# IO_Shield_With_Power_Supply_PCB.net
KiCad netlist of a schematic drawn in EAGLE
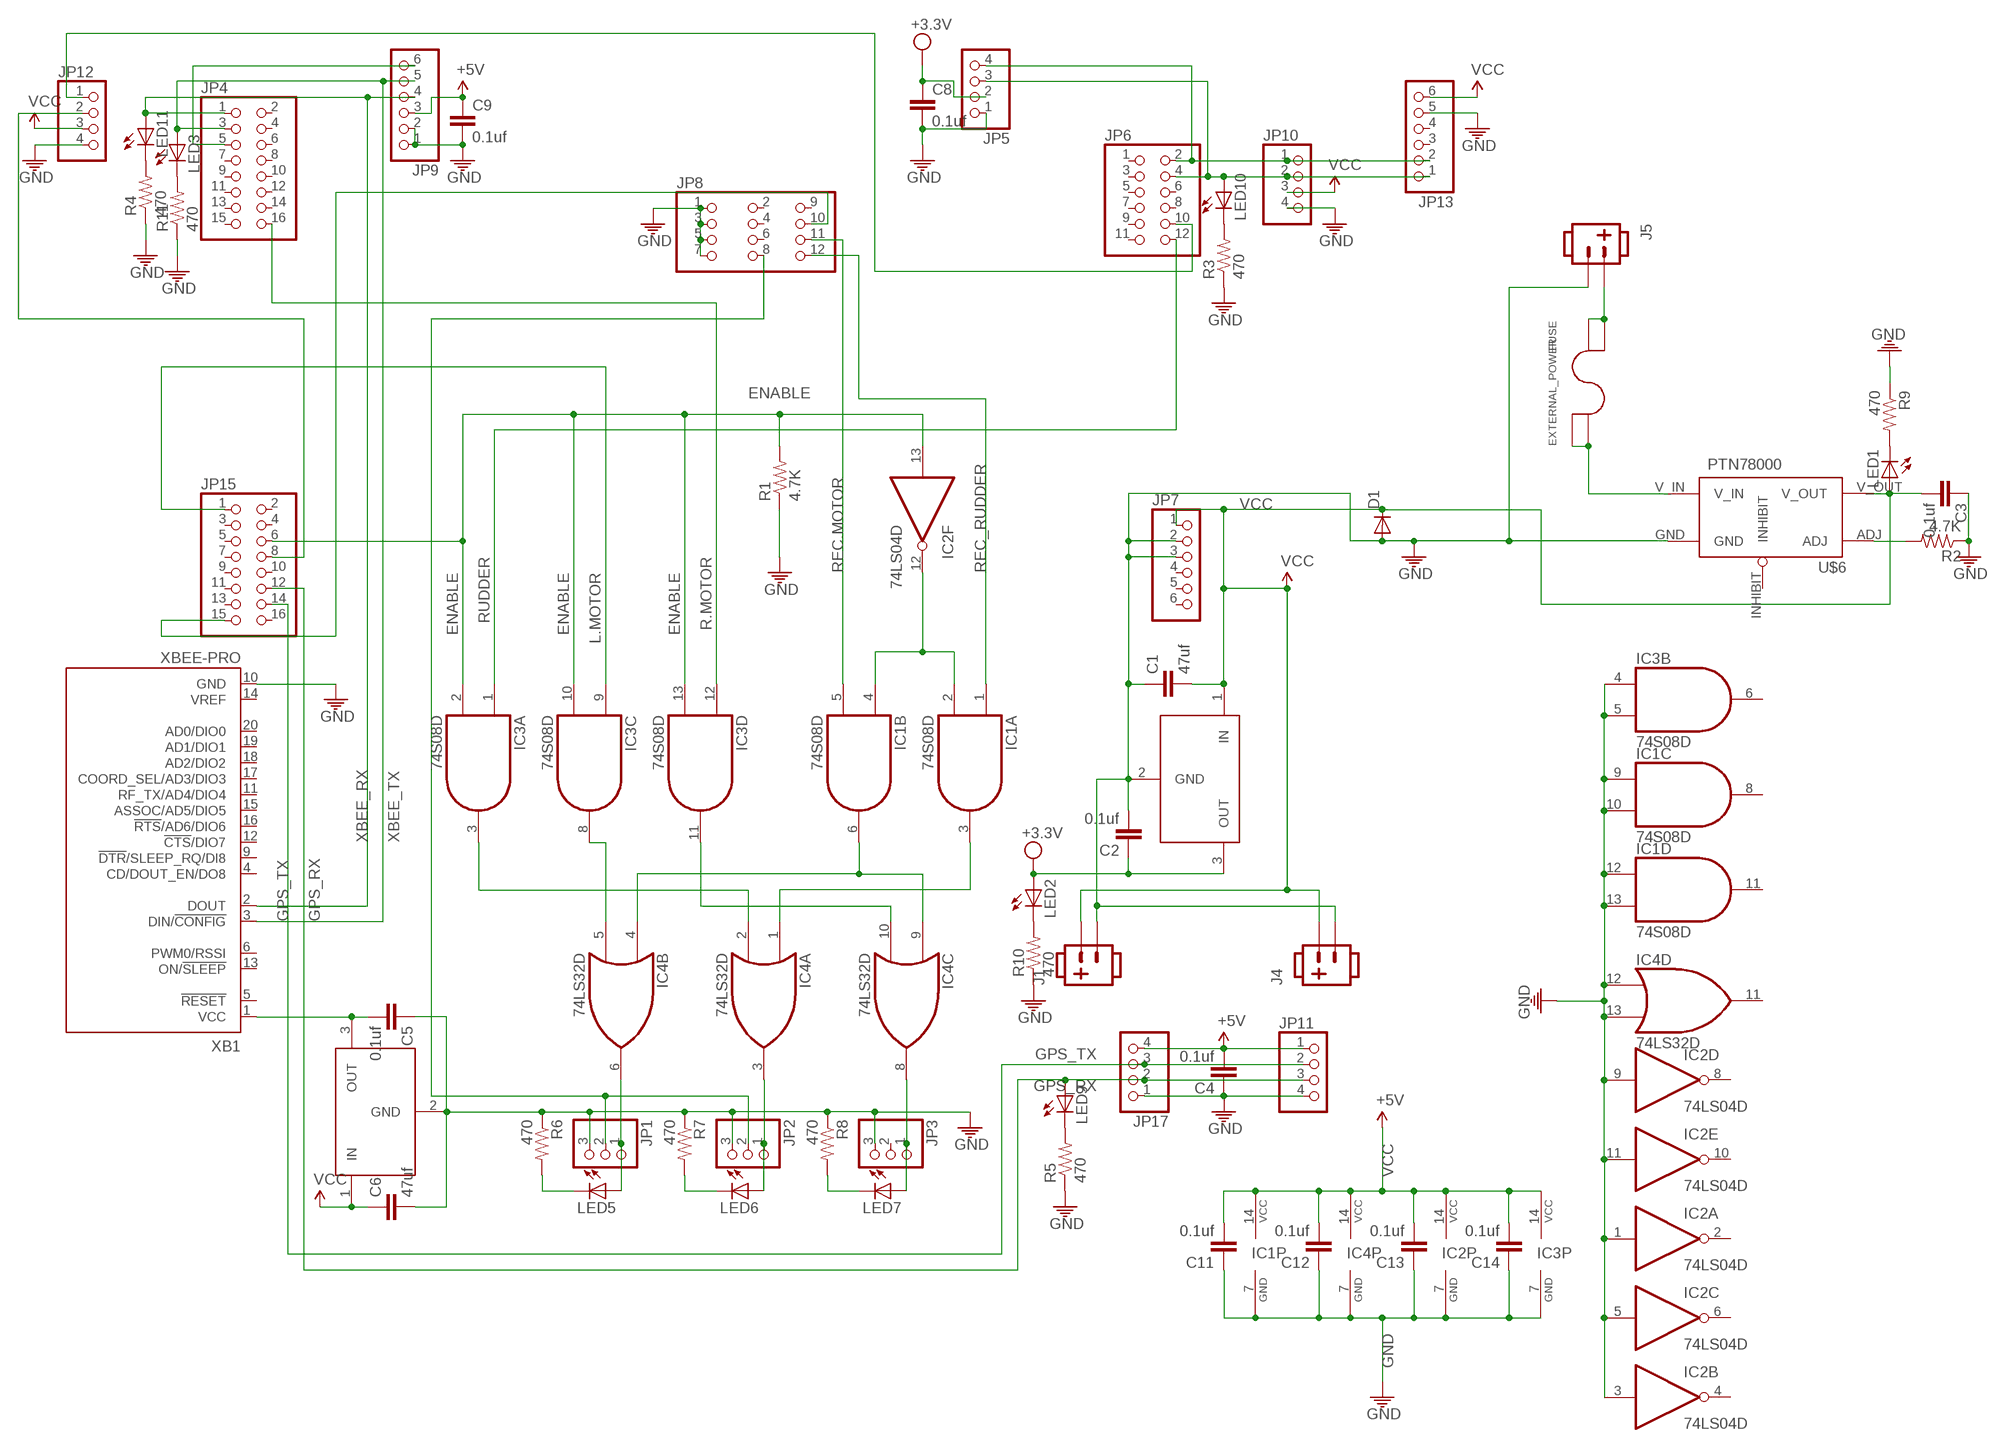
[diagram p0: schematic, sheet 1]

(export (version "E")
  (design (tool "Eeschema 10.0.6"))
  (components
    (comp (ref "C1")
      (value "47uf")
      (footprint "eagle-import:C0805")
      (libsource (lib "eagle-import") (part "C-EUC0805"))
    )
    (comp (ref "C2")
      (value "0.1uf")
      (footprint "eagle-import:C0805")
      (libsource (lib "eagle-import") (part "C-EUC0805"))
    )
    (comp (ref "C3")
      (value "0.1uf")
      (footprint "eagle-import:C0805")
      (libsource (lib "eagle-import") (part "C-EUC0805"))
    )
    (comp (ref "C4")
      (value "0.1uf")
      (footprint "eagle-import:C0805")
      (libsource (lib "eagle-import") (part "C-EUC0805"))
    )
    (comp (ref "C5")
      (value "0.1uf")
      (footprint "eagle-import:C0805")
      (libsource (lib "eagle-import") (part "C-EUC0805"))
    )
    (comp (ref "C6")
      (value "47uf")
      (footprint "eagle-import:C0805")
      (libsource (lib "eagle-import") (part "C-EUC0805"))
    )
    (comp (ref "C8")
      (value "0.1uf")
      (footprint "eagle-import:C0805")
      (libsource (lib "eagle-import") (part "C-EUC0805"))
    )
    (comp (ref "C9")
      (value "0.1uf")
      (footprint "eagle-import:C0805")
      (libsource (lib "eagle-import") (part "C-EUC0805"))
    )
    (comp (ref "C11")
      (value "0.1uf")
      (footprint "eagle-import:C0805")
      (libsource (lib "eagle-import") (part "C-EUC0805"))
    )
    (comp (ref "C12")
      (value "0.1uf")
      (footprint "eagle-import:C0805")
      (libsource (lib "eagle-import") (part "C-EUC0805"))
    )
    (comp (ref "C13")
      (value "0.1uf")
      (footprint "eagle-import:C0805")
      (libsource (lib "eagle-import") (part "C-EUC0805"))
    )
    (comp (ref "C14")
      (value "0.1uf")
      (footprint "eagle-import:C0805")
      (libsource (lib "eagle-import") (part "C-EUC0805"))
    )
    (comp (ref "D1")
      (value "DIODEPTH")
      (footprint "eagle-import:DIODE-1N4001")
      (libsource (lib "eagle-import") (part "DIODEPTH"))
    )
    (comp (ref "EXTERNAL_POWER")
      (value "FUSE")
      (footprint "eagle-import:FUSE_2AG")
      (libsource (lib "eagle-import") (part "FUSE"))
    )
    (comp (ref "IC1")
      (value "74S08D")
      (footprint "eagle-import:SO14")
      (libsource (lib "eagle-import") (part "7408DS"))
    )
    (comp (ref "IC2")
      (value "74LS04D")
      (footprint "eagle-import:SO14")
      (libsource (lib "eagle-import") (part "7404DLS"))
    )
    (comp (ref "IC3")
      (value "74S08D")
      (footprint "eagle-import:SO14")
      (libsource (lib "eagle-import") (part "7408DS"))
    )
    (comp (ref "IC4")
      (value "74LS32D")
      (footprint "eagle-import:SO14")
      (libsource (lib "eagle-import") (part "7432DLS"))
    )
    (comp (ref "J1")
      (value "POW_CONNECTFEMALE-RA")
      (footprint "eagle-import:SOCKET-FEMALE_RA-3.96MM-2")
      (libsource (lib "eagle-import") (part "POW_CONNECTFEMALE-RA"))
    )
    (comp (ref "J4")
      (value "POW_CONNECTFEMALE-RA")
      (footprint "eagle-import:SOCKET-FEMALE_RA-3.96MM-2")
      (libsource (lib "eagle-import") (part "POW_CONNECTFEMALE-RA"))
    )
    (comp (ref "J5")
      (value "POW_CONNECTFEMALE-RA")
      (footprint "eagle-import:SOCKET-FEMALE_RA-3.96MM-2")
      (libsource (lib "eagle-import") (part "POW_CONNECTFEMALE-RA"))
    )
    (comp (ref "JP1")
      (value "PINHD-1X3/90")
      (footprint "eagle-import:1X03_90")
      (libsource (lib "eagle-import") (part "PINHD-1X3/90"))
    )
    (comp (ref "JP2")
      (value "PINHD-1X3/90")
      (footprint "eagle-import:1X03_90")
      (libsource (lib "eagle-import") (part "PINHD-1X3/90"))
    )
    (comp (ref "JP3")
      (value "PINHD-1X3/90")
      (footprint "eagle-import:1X03_90")
      (libsource (lib "eagle-import") (part "PINHD-1X3/90"))
    )
    (comp (ref "JP4")
      (value "PINHD-2X8")
      (footprint "eagle-import:2X08")
      (libsource (lib "eagle-import") (part "PINHD-2X8"))
    )
    (comp (ref "JP5")
      (value "PINHD-1X4")
      (footprint "eagle-import:1X04")
      (libsource (lib "eagle-import") (part "PINHD-1X4"))
    )
    (comp (ref "JP6")
      (value "PINHD-2X6")
      (footprint "eagle-import:2X06")
      (libsource (lib "eagle-import") (part "PINHD-2X6"))
    )
    (comp (ref "JP7")
      (value "PINHD-1X6")
      (footprint "eagle-import:1X06@1")
      (libsource (lib "eagle-import") (part "pinhead_PINHD-1X6"))
    )
    (comp (ref "JP8")
      (value "PINHD-2X4")
      (footprint "eagle-import:2X04")
      (libsource (lib "eagle-import") (part "PINHD-2X4"))
    )
    (comp (ref "JP9")
      (value "PINHD-1X6")
      (footprint "eagle-import:1X06")
      (libsource (lib "eagle-import") (part "PINHD-1X6"))
    )
    (comp (ref "JP10")
      (value "PINHD-1X4/90")
      (footprint "eagle-import:1X04_90")
      (libsource (lib "eagle-import") (part "pinhead_PINHD-1X4/90"))
    )
    (comp (ref "JP11")
      (value "PINHD-1X4/90")
      (footprint "eagle-import:1X04_90")
      (libsource (lib "eagle-import") (part "pinhead_PINHD-1X4/90"))
    )
    (comp (ref "JP12")
      (value "PINHD-1X4/90")
      (footprint "eagle-import:1X04_90")
      (libsource (lib "eagle-import") (part "pinhead_PINHD-1X4/90"))
    )
    (comp (ref "JP13")
      (value "PINHD-1X6")
      (footprint "eagle-import:1X06")
      (libsource (lib "eagle-import") (part "baro_PINHD-1X6"))
    )
    (comp (ref "JP15")
      (value "PINHD-2X8")
      (footprint "eagle-import:2X08")
      (libsource (lib "eagle-import") (part "PINHD-2X8"))
    )
    (comp (ref "JP17")
      (value "PINHD-1X4")
      (footprint "eagle-import:1X04")
      (libsource (lib "eagle-import") (part "pinhead_PINHD-1X4"))
    )
    (comp (ref "LED1")
      (value "LED-FKIT-1206")
      (footprint "eagle-import:FKIT-LED-1206")
      (libsource (lib "eagle-import") (part "LED-FKIT-1206"))
    )
    (comp (ref "LED2")
      (value "LED-FKIT-1206")
      (footprint "eagle-import:FKIT-LED-1206")
      (libsource (lib "eagle-import") (part "LED-FKIT-1206"))
    )
    (comp (ref "LED3")
      (value "LED-FKIT-1206")
      (footprint "eagle-import:FKIT-LED-1206")
      (libsource (lib "eagle-import") (part "LED-FKIT-1206"))
    )
    (comp (ref "LED5")
      (value "LED-FKIT-1206")
      (footprint "eagle-import:FKIT-LED-1206")
      (libsource (lib "eagle-import") (part "LED-FKIT-1206"))
    )
    (comp (ref "LED6")
      (value "LED-FKIT-1206")
      (footprint "eagle-import:FKIT-LED-1206")
      (libsource (lib "eagle-import") (part "LED-FKIT-1206"))
    )
    (comp (ref "LED7")
      (value "LED-FKIT-1206")
      (footprint "eagle-import:FKIT-LED-1206")
      (libsource (lib "eagle-import") (part "LED-FKIT-1206"))
    )
    (comp (ref "LED9")
      (value "LED-FKIT-1206")
      (footprint "eagle-import:FKIT-LED-1206")
      (libsource (lib "eagle-import") (part "LED-FKIT-1206"))
    )
    (comp (ref "LED10")
      (value "LED-FKIT-1206")
      (footprint "eagle-import:FKIT-LED-1206")
      (libsource (lib "eagle-import") (part "LED-FKIT-1206"))
    )
    (comp (ref "LED11")
      (value "LED-FKIT-1206")
      (footprint "eagle-import:FKIT-LED-1206")
      (libsource (lib "eagle-import") (part "LED-FKIT-1206"))
    )
    (comp (ref "R1")
      (value "4.7K")
      (footprint "eagle-import:0805")
      (libsource (lib "eagle-import") (part "RESISTOR0805-RES"))
    )
    (comp (ref "R2")
      (value "4.7K")
      (footprint "eagle-import:0805")
      (libsource (lib "eagle-import") (part "RESISTOR0805-RES"))
    )
    (comp (ref "R3")
      (value "470")
      (footprint "eagle-import:0805")
      (libsource (lib "eagle-import") (part "RESISTOR0805-RES"))
    )
    (comp (ref "R4")
      (value "470")
      (footprint "eagle-import:0805")
      (libsource (lib "eagle-import") (part "RESISTOR0805-RES"))
    )
    (comp (ref "R5")
      (value "470")
      (footprint "eagle-import:0805")
      (libsource (lib "eagle-import") (part "RESISTOR0805-RES"))
    )
    (comp (ref "R6")
      (value "470")
      (footprint "eagle-import:0805")
      (libsource (lib "eagle-import") (part "RESISTOR0805-RES"))
    )
    (comp (ref "R7")
      (value "470")
      (footprint "eagle-import:0805")
      (libsource (lib "eagle-import") (part "RESISTOR0805-RES"))
    )
    (comp (ref "R8")
      (value "470")
      (footprint "eagle-import:0805")
      (libsource (lib "eagle-import") (part "RESISTOR0805-RES"))
    )
    (comp (ref "R9")
      (value "470")
      (footprint "eagle-import:0805")
      (libsource (lib "eagle-import") (part "RESISTOR0805-RES"))
    )
    (comp (ref "R10")
      (value "470")
      (footprint "eagle-import:0805")
      (libsource (lib "eagle-import") (part "RESISTOR0805-RES"))
    )
    (comp (ref "R11")
      (value "470")
      (footprint "eagle-import:0805")
      (libsource (lib "eagle-import") (part "RESISTOR0805-RES"))
    )
    (comp (ref "U$1")
      (value "LM3940IMP-3.3")
      (footprint "eagle-import:SOT223")
      (libsource (lib "eagle-import") (part "LM3940IMP-3.3"))
    )
    (comp (ref "U$6")
      (value "PTN78000")
      (footprint "eagle-import:PTN78000")
      (libsource (lib "eagle-import") (part "PTN78000THROUGH-HOLE"))
    )
    (comp (ref "U$7")
      (value "LM3940IMP-3.3")
      (footprint "eagle-import:SOT223")
      (libsource (lib "eagle-import") (part "LM3940IMP-3.3"))
    )
    (comp (ref "XB1")
      (value "XBEE-PRO")
      (footprint "eagle-import:XBEE-PRO")
      (fields (field (name "MPN") "XBP24-AWI-001"))
      (libsource (lib "eagle-import") (part "XBEE-PRO"))
    )
  )
  (nets
    (net (code "1") (name "+3.3V") (class "Default")
      (node (ref "C2") (pin "1") (pinfunction "1_1") (pintype "passive"))
      (node (ref "C8") (pin "1") (pinfunction "1_1") (pintype "passive"))
      (node (ref "JP5") (pin "2") (pinfunction "2_2") (pintype "passive"))
      (node (ref "LED2") (pin "A") (pinfunction "A_A") (pintype "passive"))
      (node (ref "U$1") (pin "3") (pinfunction "OUT_3") (pintype "power_in"))
    )
    (net (code "2") (name "+5V") (class "Default")
      (node (ref "C1") (pin "2") (pinfunction "2_2") (pintype "passive"))
      (node (ref "C11") (pin "2") (pinfunction "2_2") (pintype "passive"))
      (node (ref "C12") (pin "2") (pinfunction "2_2") (pintype "passive"))
      (node (ref "C13") (pin "2") (pinfunction "2_2") (pintype "passive"))
      (node (ref "C14") (pin "2") (pinfunction "2_2") (pintype "passive"))
      (node (ref "C3") (pin "2") (pinfunction "2_2") (pintype "passive"))
      (node (ref "C4") (pin "2") (pinfunction "2_2") (pintype "passive"))
      (node (ref "C6") (pin "1") (pinfunction "1_1") (pintype "passive"))
      (node (ref "C9") (pin "1") (pinfunction "1_1") (pintype "passive"))
      (node (ref "D1") (pin "C") (pinfunction "C_C") (pintype "passive"))
      (node (ref "IC1") (pin "14") (pinfunction "VCC_14") (pintype "power_in"))
      (node (ref "IC2") (pin "14") (pinfunction "VCC_14") (pintype "power_in"))
      (node (ref "IC3") (pin "14") (pinfunction "VCC_14") (pintype "power_in"))
      (node (ref "IC4") (pin "14") (pinfunction "VCC_14") (pintype "power_in"))
      (node (ref "J1") (pin "1") (pinfunction "1_1") (pintype "passive"))
      (node (ref "J4") (pin "1") (pinfunction "1_1") (pintype "passive"))
      (node (ref "JP10") (pin "3") (pinfunction "3_3") (pintype "passive"))
      (node (ref "JP11") (pin "1") (pinfunction "1_1") (pintype "passive"))
      (node (ref "JP12") (pin "3") (pinfunction "3_3") (pintype "passive"))
      (node (ref "JP13") (pin "6") (pinfunction "6_6") (pintype "passive"))
      (node (ref "JP17") (pin "4") (pinfunction "4_4") (pintype "passive"))
      (node (ref "JP7") (pin "1") (pinfunction "1_1") (pintype "passive"))
      (node (ref "JP9") (pin "3") (pinfunction "3_3") (pintype "passive"))
      (node (ref "LED1") (pin "A") (pinfunction "A_A") (pintype "passive"))
      (node (ref "U$1") (pin "1") (pinfunction "IN_1") (pintype "power_in"))
      (node (ref "U$6") (pin "V_OUT") (pinfunction "V_OUT_V_OUT") (pintype "output"))
      (node (ref "U$7") (pin "1") (pinfunction "IN_1") (pintype "power_in"))
    )
    (net (code "3") (name "/ENABLE") (class "Default")
      (node (ref "IC2") (pin "13") (pinfunction "I_13") (pintype "input"))
      (node (ref "IC3") (pin "10") (pinfunction "I1_10") (pintype "input"))
      (node (ref "IC3") (pin "13") (pinfunction "I1_13") (pintype "input"))
      (node (ref "IC3") (pin "2") (pinfunction "I1_2") (pintype "input"))
      (node (ref "JP15") (pin "6") (pinfunction "6_6") (pintype "passive"))
      (node (ref "R1") (pin "2") (pinfunction "2_2") (pintype "passive"))
    )
    (net (code "4") (name "/GPS_RX") (class "Default")
      (node (ref "JP11") (pin "3") (pinfunction "3_3") (pintype "passive"))
      (node (ref "JP15") (pin "12") (pinfunction "12_12") (pintype "passive"))
      (node (ref "JP17") (pin "2") (pinfunction "2_2") (pintype "passive"))
      (node (ref "LED9") (pin "A") (pinfunction "A_A") (pintype "passive"))
    )
    (net (code "5") (name "/GPS_TX") (class "Default")
      (node (ref "JP11") (pin "2") (pinfunction "2_2") (pintype "passive"))
      (node (ref "JP15") (pin "14") (pinfunction "14_14") (pintype "passive"))
      (node (ref "JP17") (pin "3") (pinfunction "3_3") (pintype "passive"))
    )
    (net (code "6") (name "/L.MOTOR") (class "Default")
      (node (ref "IC3") (pin "9") (pinfunction "I0_9") (pintype "input"))
      (node (ref "JP15") (pin "1") (pinfunction "1_1") (pintype "passive"))
    )
    (net (code "7") (name "/R.MOTOR") (class "Default")
      (node (ref "IC3") (pin "12") (pinfunction "I0_12") (pintype "input"))
      (node (ref "JP4") (pin "16") (pinfunction "16_16") (pintype "passive"))
    )
    (net (code "8") (name "/REC.MOTOR") (class "Default")
      (node (ref "IC1") (pin "5") (pinfunction "I1_5") (pintype "input"))
      (node (ref "JP8") (pin "11") (pinfunction "11_11") (pintype "passive"))
    )
    (net (code "9") (name "/REC_RUDDER") (class "Default")
      (node (ref "IC1") (pin "1") (pinfunction "I0_1") (pintype "input"))
      (node (ref "JP8") (pin "12") (pinfunction "12_12") (pintype "passive"))
    )
    (net (code "10") (name "/RUDDER") (class "Default")
      (node (ref "IC3") (pin "1") (pinfunction "I0_1") (pintype "input"))
      (node (ref "JP6") (pin "12") (pinfunction "12_12") (pintype "passive"))
    )
    (net (code "11") (name "/XBEE_RX") (class "Default")
      (node (ref "JP4") (pin "1") (pinfunction "1_1") (pintype "passive"))
      (node (ref "JP9") (pin "4") (pinfunction "4_4") (pintype "passive"))
      (node (ref "LED11") (pin "A") (pinfunction "A_A") (pintype "passive"))
      (node (ref "XB1") (pin "2") (pinfunction "DOUT_2") (pintype "output"))
    )
    (net (code "12") (name "/XBEE_TX") (class "Default")
      (node (ref "JP4") (pin "3") (pinfunction "3_3") (pintype "passive"))
      (node (ref "JP9") (pin "5") (pinfunction "5_5") (pintype "passive"))
      (node (ref "LED3") (pin "A") (pinfunction "A_A") (pintype "passive"))
      (node (ref "XB1") (pin "3") (pinfunction "DIN/~{CONFIG}_3") (pintype "input"))
    )
    (net (code "13") (name "GND") (class "Default")
      (node (ref "C1") (pin "1") (pinfunction "1_1") (pintype "passive"))
      (node (ref "C11") (pin "1") (pinfunction "1_1") (pintype "passive"))
      (node (ref "C12") (pin "1") (pinfunction "1_1") (pintype "passive"))
      (node (ref "C13") (pin "1") (pinfunction "1_1") (pintype "passive"))
      (node (ref "C14") (pin "1") (pinfunction "1_1") (pintype "passive"))
      (node (ref "C2") (pin "2") (pinfunction "2_2") (pintype "passive"))
      (node (ref "C3") (pin "1") (pinfunction "1_1") (pintype "passive"))
      (node (ref "C4") (pin "1") (pinfunction "1_1") (pintype "passive"))
      (node (ref "C5") (pin "1") (pinfunction "1_1") (pintype "passive"))
      (node (ref "C6") (pin "2") (pinfunction "2_2") (pintype "passive"))
      (node (ref "C8") (pin "2") (pinfunction "2_2") (pintype "passive"))
      (node (ref "C9") (pin "2") (pinfunction "2_2") (pintype "passive"))
      (node (ref "D1") (pin "A") (pinfunction "A_A") (pintype "passive"))
      (node (ref "IC1") (pin "10") (pinfunction "I1_10") (pintype "input"))
      (node (ref "IC1") (pin "12") (pinfunction "I0_12") (pintype "input"))
      (node (ref "IC1") (pin "13") (pinfunction "I1_13") (pintype "input"))
      (node (ref "IC1") (pin "7") (pinfunction "GND_7") (pintype "power_in"))
      (node (ref "IC1") (pin "9") (pinfunction "I0_9") (pintype "input"))
      (node (ref "IC2") (pin "1") (pinfunction "I_1") (pintype "input"))
      (node (ref "IC2") (pin "11") (pinfunction "I_11") (pintype "input"))
      (node (ref "IC2") (pin "3") (pinfunction "I_3") (pintype "input"))
      (node (ref "IC2") (pin "5") (pinfunction "I_5") (pintype "input"))
      (node (ref "IC2") (pin "7") (pinfunction "GND_7") (pintype "power_in"))
      (node (ref "IC2") (pin "9") (pinfunction "I_9") (pintype "input"))
      (node (ref "IC3") (pin "4") (pinfunction "I0_4") (pintype "input"))
      (node (ref "IC3") (pin "5") (pinfunction "I1_5") (pintype "input"))
      (node (ref "IC3") (pin "7") (pinfunction "GND_7") (pintype "power_in"))
      (node (ref "IC4") (pin "12") (pinfunction "I0_12") (pintype "input"))
      (node (ref "IC4") (pin "13") (pinfunction "I1_13") (pintype "input"))
      (node (ref "IC4") (pin "7") (pinfunction "GND_7") (pintype "power_in"))
      (node (ref "J1") (pin "2") (pinfunction "2_2") (pintype "passive"))
      (node (ref "J4") (pin "2") (pinfunction "2_2") (pintype "passive"))
      (node (ref "J5") (pin "2") (pinfunction "2_2") (pintype "passive"))
      (node (ref "JP1") (pin "3") (pinfunction "3_3") (pintype "passive"))
      (node (ref "JP10") (pin "4") (pinfunction "4_4") (pintype "passive"))
      (node (ref "JP11") (pin "4") (pinfunction "4_4") (pintype "passive"))
      (node (ref "JP12") (pin "4") (pinfunction "4_4") (pintype "passive"))
      (node (ref "JP13") (pin "5") (pinfunction "5_5") (pintype "passive"))
      (node (ref "JP17") (pin "1") (pinfunction "1_1") (pintype "passive"))
      (node (ref "JP2") (pin "3") (pinfunction "3_3") (pintype "passive"))
      (node (ref "JP3") (pin "3") (pinfunction "3_3") (pintype "passive"))
      (node (ref "JP5") (pin "1") (pinfunction "1_1") (pintype "passive"))
      (node (ref "JP7") (pin "2") (pinfunction "2_2") (pintype "passive"))
      (node (ref "JP7") (pin "3") (pinfunction "3_3") (pintype "passive"))
      (node (ref "JP8") (pin "1") (pinfunction "1_1") (pintype "passive"))
      (node (ref "JP8") (pin "3") (pinfunction "3_3") (pintype "passive"))
      (node (ref "JP8") (pin "5") (pinfunction "5_5") (pintype "passive"))
      (node (ref "JP8") (pin "7") (pinfunction "7_7") (pintype "passive"))
      (node (ref "JP9") (pin "1") (pinfunction "1_1") (pintype "passive"))
      (node (ref "JP9") (pin "2") (pinfunction "2_2") (pintype "passive"))
      (node (ref "R1") (pin "1") (pinfunction "1_1") (pintype "passive"))
      (node (ref "R10") (pin "1") (pinfunction "1_1") (pintype "passive"))
      (node (ref "R11") (pin "1") (pinfunction "1_1") (pintype "passive"))
      (node (ref "R2") (pin "1") (pinfunction "1_1") (pintype "passive"))
      (node (ref "R3") (pin "1") (pinfunction "1_1") (pintype "passive"))
      (node (ref "R4") (pin "1") (pinfunction "1_1") (pintype "passive"))
      (node (ref "R5") (pin "1") (pinfunction "1_1") (pintype "passive"))
      (node (ref "R6") (pin "1") (pinfunction "1_1") (pintype "passive"))
      (node (ref "R7") (pin "1") (pinfunction "1_1") (pintype "passive"))
      (node (ref "R8") (pin "1") (pinfunction "1_1") (pintype "passive"))
      (node (ref "R9") (pin "1") (pinfunction "1_1") (pintype "passive"))
      (node (ref "U$1") (pin "2") (pinfunction "GND_2") (pintype "power_in"))
      (node (ref "U$6") (pin "GND") (pinfunction "GND_GND") (pintype "power_in"))
      (node (ref "U$7") (pin "2") (pinfunction "GND_2") (pintype "power_in"))
      (node (ref "XB1") (pin "10") (pinfunction "GND_10") (pintype "power_in"))
    )
    (net (code "14") (name "Net-(EXTERNAL_POWER-1)") (class "Default")
      (node (ref "EXTERNAL_POWER") (pin "P$1") (pinfunction "1_P$1") (pintype "bidirectional"))
      (node (ref "EXTERNAL_POWER") (pin "P$2") (pinfunction "2_P$2") (pintype "bidirectional"))
      (node (ref "U$6") (pin "V_IN") (pinfunction "V_IN_V_IN") (pintype "power_in"))
    )
    (net (code "15") (name "Net-(EXTERNAL_POWER-3)") (class "Default")
      (node (ref "EXTERNAL_POWER") (pin "P$3") (pinfunction "3_P$3") (pintype "bidirectional"))
      (node (ref "EXTERNAL_POWER") (pin "P$4") (pinfunction "4_P$4") (pintype "bidirectional"))
      (node (ref "J5") (pin "1") (pinfunction "1_1") (pintype "passive"))
    )
    (net (code "16") (name "Net-(IC1A-I1)") (class "Default")
      (node (ref "IC1") (pin "2") (pinfunction "I1_2") (pintype "input"))
      (node (ref "IC1") (pin "4") (pinfunction "I0_4") (pintype "input"))
      (node (ref "IC2") (pin "12") (pinfunction "O_12") (pintype "output"))
    )
    (net (code "17") (name "Net-(IC1A-O)") (class "Default")
      (node (ref "IC1") (pin "3") (pinfunction "O_3") (pintype "output"))
      (node (ref "IC4") (pin "1") (pinfunction "I0_1") (pintype "input"))
    )
    (net (code "18") (name "Net-(IC1B-O)") (class "Default")
      (node (ref "IC1") (pin "6") (pinfunction "O_6") (pintype "output"))
      (node (ref "IC4") (pin "4") (pinfunction "I0_4") (pintype "input"))
      (node (ref "IC4") (pin "9") (pinfunction "I0_9") (pintype "input"))
    )
    (net (code "19") (name "Net-(IC3A-O)") (class "Default")
      (node (ref "IC3") (pin "3") (pinfunction "O_3") (pintype "output"))
      (node (ref "IC4") (pin "2") (pinfunction "I1_2") (pintype "input"))
    )
    (net (code "20") (name "Net-(IC3C-O)") (class "Default")
      (node (ref "IC3") (pin "8") (pinfunction "O_8") (pintype "output"))
      (node (ref "IC4") (pin "5") (pinfunction "I1_5") (pintype "input"))
    )
    (net (code "21") (name "Net-(IC3D-O)") (class "Default")
      (node (ref "IC3") (pin "11") (pinfunction "O_11") (pintype "output"))
      (node (ref "IC4") (pin "10") (pinfunction "I1_10") (pintype "input"))
    )
    (net (code "22") (name "Net-(IC4A-O)") (class "Default")
      (node (ref "IC4") (pin "3") (pinfunction "O_3") (pintype "output"))
      (node (ref "JP2") (pin "1") (pinfunction "1_1") (pintype "passive"))
      (node (ref "LED6") (pin "A") (pinfunction "A_A") (pintype "passive"))
    )
    (net (code "23") (name "Net-(IC4B-O)") (class "Default")
      (node (ref "IC4") (pin "6") (pinfunction "O_6") (pintype "output"))
      (node (ref "JP1") (pin "1") (pinfunction "1_1") (pintype "passive"))
      (node (ref "LED5") (pin "A") (pinfunction "A_A") (pintype "passive"))
    )
    (net (code "24") (name "Net-(IC4C-O)") (class "Default")
      (node (ref "IC4") (pin "8") (pinfunction "O_8") (pintype "output"))
      (node (ref "JP3") (pin "1") (pinfunction "1_1") (pintype "passive"))
      (node (ref "LED7") (pin "A") (pinfunction "A_A") (pintype "passive"))
    )
    (net (code "25") (name "Net-(JP1-Pad2)") (class "Default")
      (node (ref "JP1") (pin "2") (pinfunction "2_2") (pintype "passive"))
      (node (ref "JP2") (pin "2") (pinfunction "2_2") (pintype "passive"))
      (node (ref "JP8") (pin "8") (pinfunction "8_8") (pintype "passive"))
    )
    (net (code "26") (name "Net-(JP4-Pad5)") (class "Default")
      (node (ref "JP4") (pin "5") (pinfunction "5_5") (pintype "passive"))
      (node (ref "JP9") (pin "6") (pinfunction "6_6") (pintype "passive"))
    )
    (net (code "27") (name "Net-(JP8-9)") (class "Default")
      (node (ref "JP15") (pin "15") (pinfunction "15_15") (pintype "passive"))
      (node (ref "JP8") (pin "10") (pinfunction "9_10") (pintype "passive"))
    )
    (net (code "28") (name "Net-(JP10-Pad1)") (class "Default")
      (node (ref "JP10") (pin "1") (pinfunction "1_1") (pintype "passive"))
      (node (ref "JP13") (pin "2") (pinfunction "2_2") (pintype "passive"))
      (node (ref "JP5") (pin "4") (pinfunction "4_4") (pintype "passive"))
      (node (ref "JP6") (pin "2") (pinfunction "2_2") (pintype "passive"))
    )
    (net (code "29") (name "Net-(JP10-Pad2)") (class "Default")
      (node (ref "JP10") (pin "2") (pinfunction "2_2") (pintype "passive"))
      (node (ref "JP13") (pin "1") (pinfunction "1_1") (pintype "passive"))
      (node (ref "JP5") (pin "3") (pinfunction "3_3") (pintype "passive"))
      (node (ref "JP6") (pin "4") (pinfunction "4_4") (pintype "passive"))
      (node (ref "LED10") (pin "A") (pinfunction "A_A") (pintype "passive"))
    )
    (net (code "30") (name "Net-(JP12-Pad1)") (class "Default")
      (node (ref "JP12") (pin "1") (pinfunction "1_1") (pintype "passive"))
      (node (ref "JP6") (pin "10") (pinfunction "10_10") (pintype "passive"))
    )
    (net (code "31") (name "Net-(JP12-Pad2)") (class "Default")
      (node (ref "JP12") (pin "2") (pinfunction "2_2") (pintype "passive"))
      (node (ref "JP15") (pin "8") (pinfunction "8_8") (pintype "passive"))
    )
    (net (code "32") (name "Net-(LED1-PadC)") (class "Default")
      (node (ref "LED1") (pin "C") (pinfunction "C_C") (pintype "passive"))
      (node (ref "R9") (pin "2") (pinfunction "2_2") (pintype "passive"))
    )
    (net (code "33") (name "Net-(LED2-PadC)") (class "Default")
      (node (ref "LED2") (pin "C") (pinfunction "C_C") (pintype "passive"))
      (node (ref "R10") (pin "2") (pinfunction "2_2") (pintype "passive"))
    )
    (net (code "34") (name "Net-(LED3-PadC)") (class "Default")
      (node (ref "LED3") (pin "C") (pinfunction "C_C") (pintype "passive"))
      (node (ref "R11") (pin "2") (pinfunction "2_2") (pintype "passive"))
    )
    (net (code "35") (name "Net-(LED5-PadC)") (class "Default")
      (node (ref "LED5") (pin "C") (pinfunction "C_C") (pintype "passive"))
      (node (ref "R6") (pin "2") (pinfunction "2_2") (pintype "passive"))
    )
    (net (code "36") (name "Net-(LED6-PadC)") (class "Default")
      (node (ref "LED6") (pin "C") (pinfunction "C_C") (pintype "passive"))
      (node (ref "R7") (pin "2") (pinfunction "2_2") (pintype "passive"))
    )
    (net (code "37") (name "Net-(LED7-PadC)") (class "Default")
      (node (ref "LED7") (pin "C") (pinfunction "C_C") (pintype "passive"))
      (node (ref "R8") (pin "2") (pinfunction "2_2") (pintype "passive"))
    )
    (net (code "38") (name "Net-(LED9-PadC)") (class "Default")
      (node (ref "LED9") (pin "C") (pinfunction "C_C") (pintype "passive"))
      (node (ref "R5") (pin "2") (pinfunction "2_2") (pintype "passive"))
    )
    (net (code "39") (name "Net-(LED10-PadC)") (class "Default")
      (node (ref "LED10") (pin "C") (pinfunction "C_C") (pintype "passive"))
      (node (ref "R3") (pin "2") (pinfunction "2_2") (pintype "passive"))
    )
    (net (code "40") (name "Net-(LED11-PadC)") (class "Default")
      (node (ref "LED11") (pin "C") (pinfunction "C_C") (pintype "passive"))
      (node (ref "R4") (pin "2") (pinfunction "2_2") (pintype "passive"))
    )
    (net (code "41") (name "Net-(R2-Pad2)") (class "Default")
      (node (ref "R2") (pin "2") (pinfunction "2_2") (pintype "passive"))
      (node (ref "U$6") (pin "ADJ") (pinfunction "ADJ_ADJ") (pintype "input"))
    )
    (net (code "42") (name "Net-(U$7-OUT)") (class "Default")
      (node (ref "C5") (pin "2") (pinfunction "2_2") (pintype "passive"))
      (node (ref "U$7") (pin "3") (pinfunction "OUT_3") (pintype "power_in"))
      (node (ref "XB1") (pin "1") (pinfunction "VCC_1") (pintype "power_in"))
    )
    (net (code "43") (name "unconnected-(IC1C-O-Pad8)") (class "Default")
      (node (ref "IC1") (pin "8") (pinfunction "O_8") (pintype "output"))
    )
    (net (code "44") (name "unconnected-(IC1D-O-Pad11)") (class "Default")
      (node (ref "IC1") (pin "11") (pinfunction "O_11") (pintype "output"))
    )
    (net (code "45") (name "unconnected-(IC2A-O-Pad2)") (class "Default")
      (node (ref "IC2") (pin "2") (pinfunction "O_2") (pintype "output"))
    )
    (net (code "46") (name "unconnected-(IC2B-O-Pad4)") (class "Default")
      (node (ref "IC2") (pin "4") (pinfunction "O_4") (pintype "output"))
    )
    (net (code "47") (name "unconnected-(IC2C-O-Pad6)") (class "Default")
      (node (ref "IC2") (pin "6") (pinfunction "O_6") (pintype "output"))
    )
    (net (code "48") (name "unconnected-(IC2D-O-Pad8)") (class "Default")
      (node (ref "IC2") (pin "8") (pinfunction "O_8") (pintype "output"))
    )
    (net (code "49") (name "unconnected-(IC2E-O-Pad10)") (class "Default")
      (node (ref "IC2") (pin "10") (pinfunction "O_10") (pintype "output"))
    )
    (net (code "50") (name "unconnected-(IC3B-O-Pad6)") (class "Default")
      (node (ref "IC3") (pin "6") (pinfunction "O_6") (pintype "output"))
    )
    (net (code "51") (name "unconnected-(IC4D-O-Pad11)") (class "Default")
      (node (ref "IC4") (pin "11") (pinfunction "O_11") (pintype "output"))
    )
    (net (code "52") (name "unconnected-(JP3-Pad2)") (class "Default")
      (node (ref "JP3") (pin "2") (pinfunction "2_2") (pintype "passive"))
    )
    (net (code "53") (name "unconnected-(JP4-Pad2)") (class "Default")
      (node (ref "JP4") (pin "2") (pinfunction "2_2") (pintype "passive"))
    )
    (net (code "54") (name "unconnected-(JP4-Pad4)") (class "Default")
      (node (ref "JP4") (pin "4") (pinfunction "4_4") (pintype "passive"))
    )
    (net (code "55") (name "unconnected-(JP4-Pad6)") (class "Default")
      (node (ref "JP4") (pin "6") (pinfunction "6_6") (pintype "passive"))
    )
    (net (code "56") (name "unconnected-(JP4-Pad7)") (class "Default")
      (node (ref "JP4") (pin "7") (pinfunction "7_7") (pintype "passive"))
    )
    (net (code "57") (name "unconnected-(JP4-Pad8)") (class "Default")
      (node (ref "JP4") (pin "8") (pinfunction "8_8") (pintype "passive"))
    )
    (net (code "58") (name "unconnected-(JP4-Pad9)") (class "Default")
      (node (ref "JP4") (pin "9") (pinfunction "9_9") (pintype "passive"))
    )
    (net (code "59") (name "unconnected-(JP4-Pad10)") (class "Default")
      (node (ref "JP4") (pin "10") (pinfunction "10_10") (pintype "passive"))
    )
    (net (code "60") (name "unconnected-(JP4-Pad11)") (class "Default")
      (node (ref "JP4") (pin "11") (pinfunction "11_11") (pintype "passive"))
    )
    (net (code "61") (name "unconnected-(JP4-Pad12)") (class "Default")
      (node (ref "JP4") (pin "12") (pinfunction "12_12") (pintype "passive"))
    )
    (net (code "62") (name "unconnected-(JP4-Pad13)") (class "Default")
      (node (ref "JP4") (pin "13") (pinfunction "13_13") (pintype "passive"))
    )
    (net (code "63") (name "unconnected-(JP4-Pad14)") (class "Default")
      (node (ref "JP4") (pin "14") (pinfunction "14_14") (pintype "passive"))
    )
    (net (code "64") (name "unconnected-(JP4-Pad15)") (class "Default")
      (node (ref "JP4") (pin "15") (pinfunction "15_15") (pintype "passive"))
    )
    (net (code "65") (name "unconnected-(JP6-Pad1)") (class "Default")
      (node (ref "JP6") (pin "1") (pinfunction "1_1") (pintype "passive"))
    )
    (net (code "66") (name "unconnected-(JP6-Pad3)") (class "Default")
      (node (ref "JP6") (pin "3") (pinfunction "3_3") (pintype "passive"))
    )
    (net (code "67") (name "unconnected-(JP6-Pad5)") (class "Default")
      (node (ref "JP6") (pin "5") (pinfunction "5_5") (pintype "passive"))
    )
    (net (code "68") (name "unconnected-(JP6-Pad6)") (class "Default")
      (node (ref "JP6") (pin "6") (pinfunction "6_6") (pintype "passive"))
    )
    (net (code "69") (name "unconnected-(JP6-Pad7)") (class "Default")
      (node (ref "JP6") (pin "7") (pinfunction "7_7") (pintype "passive"))
    )
    (net (code "70") (name "unconnected-(JP6-Pad8)") (class "Default")
      (node (ref "JP6") (pin "8") (pinfunction "8_8") (pintype "passive"))
    )
    (net (code "71") (name "unconnected-(JP6-Pad9)") (class "Default")
      (node (ref "JP6") (pin "9") (pinfunction "9_9") (pintype "passive"))
    )
    (net (code "72") (name "unconnected-(JP6-Pad11)") (class "Default")
      (node (ref "JP6") (pin "11") (pinfunction "11_11") (pintype "passive"))
    )
    (net (code "73") (name "unconnected-(JP7-Pad4)") (class "Default")
      (node (ref "JP7") (pin "4") (pinfunction "4_4") (pintype "passive"))
    )
    (net (code "74") (name "unconnected-(JP7-Pad5)") (class "Default")
      (node (ref "JP7") (pin "5") (pinfunction "5_5") (pintype "passive"))
    )
    (net (code "75") (name "unconnected-(JP7-Pad6)") (class "Default")
      (node (ref "JP7") (pin "6") (pinfunction "6_6") (pintype "passive"))
    )
    (net (code "76") (name "unconnected-(JP8-10-Pad9)") (class "Default")
      (node (ref "JP8") (pin "9") (pinfunction "10_9") (pintype "passive"))
    )
    (net (code "77") (name "unconnected-(JP8-Pad2)") (class "Default")
      (node (ref "JP8") (pin "2") (pinfunction "2_2") (pintype "passive"))
    )
    (net (code "78") (name "unconnected-(JP8-Pad4)") (class "Default")
      (node (ref "JP8") (pin "4") (pinfunction "4_4") (pintype "passive"))
    )
    (net (code "79") (name "unconnected-(JP8-Pad6)") (class "Default")
      (node (ref "JP8") (pin "6") (pinfunction "6_6") (pintype "passive"))
    )
    (net (code "80") (name "unconnected-(JP13-Pad3)") (class "Default")
      (node (ref "JP13") (pin "3") (pinfunction "3_3") (pintype "passive"))
    )
    (net (code "81") (name "unconnected-(JP13-Pad4)") (class "Default")
      (node (ref "JP13") (pin "4") (pinfunction "4_4") (pintype "passive"))
    )
    (net (code "82") (name "unconnected-(JP15-Pad2)") (class "Default")
      (node (ref "JP15") (pin "2") (pinfunction "2_2") (pintype "passive"))
    )
    (net (code "83") (name "unconnected-(JP15-Pad3)") (class "Default")
      (node (ref "JP15") (pin "3") (pinfunction "3_3") (pintype "passive"))
    )
    (net (code "84") (name "unconnected-(JP15-Pad4)") (class "Default")
      (node (ref "JP15") (pin "4") (pinfunction "4_4") (pintype "passive"))
    )
    (net (code "85") (name "unconnected-(JP15-Pad5)") (class "Default")
      (node (ref "JP15") (pin "5") (pinfunction "5_5") (pintype "passive"))
    )
    (net (code "86") (name "unconnected-(JP15-Pad7)") (class "Default")
      (node (ref "JP15") (pin "7") (pinfunction "7_7") (pintype "passive"))
    )
    (net (code "87") (name "unconnected-(JP15-Pad9)") (class "Default")
      (node (ref "JP15") (pin "9") (pinfunction "9_9") (pintype "passive"))
    )
    (net (code "88") (name "unconnected-(JP15-Pad10)") (class "Default")
      (node (ref "JP15") (pin "10") (pinfunction "10_10") (pintype "passive"))
    )
    (net (code "89") (name "unconnected-(JP15-Pad11)") (class "Default")
      (node (ref "JP15") (pin "11") (pinfunction "11_11") (pintype "passive"))
    )
    (net (code "90") (name "unconnected-(JP15-Pad13)") (class "Default")
      (node (ref "JP15") (pin "13") (pinfunction "13_13") (pintype "passive"))
    )
    (net (code "91") (name "unconnected-(JP15-Pad16)") (class "Default")
      (node (ref "JP15") (pin "16") (pinfunction "16_16") (pintype "passive"))
    )
    (net (code "92") (name "unconnected-(U$6-PadINHIBIT)") (class "Default")
      (node (ref "U$6") (pin "INHIBIT") (pinfunction "INHIBIT_INHIBIT") (pintype "input"))
    )
    (net (code "93") (name "unconnected-(XB1-AD0{slash}DIO0-Pad20)") (class "Default")
      (node (ref "XB1") (pin "20") (pinfunction "AD0/DIO0_20") (pintype "bidirectional"))
    )
    (net (code "94") (name "unconnected-(XB1-AD1{slash}DIO1-Pad19)") (class "Default")
      (node (ref "XB1") (pin "19") (pinfunction "AD1/DIO1_19") (pintype "bidirectional"))
    )
    (net (code "95") (name "unconnected-(XB1-AD2{slash}DIO2-Pad18)") (class "Default")
      (node (ref "XB1") (pin "18") (pinfunction "AD2/DIO2_18") (pintype "bidirectional"))
    )
    (net (code "96") (name "unconnected-(XB1-ASSOC{slash}AD5{slash}DIO5-Pad15)") (class "Default")
      (node (ref "XB1") (pin "15") (pinfunction "ASSOC/AD5/DIO5_15") (pintype "bidirectional"))
    )
    (net (code "97") (name "unconnected-(XB1-CD{slash}DOUT_EN{slash}DO8-Pad4)") (class "Default")
      (node (ref "XB1") (pin "4") (pinfunction "CD/DOUT_EN/DO8_4") (pintype "output"))
    )
    (net (code "98") (name "unconnected-(XB1-COORD_SEL{slash}AD3{slash}DIO3-Pad17)") (class "Default")
      (node (ref "XB1") (pin "17") (pinfunction "COORD_SEL/AD3/DIO3_17") (pintype "bidirectional"))
    )
    (net (code "99") (name "unconnected-(XB1-ON{slash}~{SLEEP}-Pad13)") (class "Default")
      (node (ref "XB1") (pin "13") (pinfunction "ON/~{SLEEP}_13") (pintype "output"))
    )
    (net (code "100") (name "unconnected-(XB1-PWM0{slash}RSSI-Pad6)") (class "Default")
      (node (ref "XB1") (pin "6") (pinfunction "PWM0/RSSI_6") (pintype "output"))
    )
    (net (code "101") (name "unconnected-(XB1-RF_TX{slash}AD4{slash}DIO4-Pad11)") (class "Default")
      (node (ref "XB1") (pin "11") (pinfunction "RF_TX/AD4/DIO4_11") (pintype "bidirectional"))
    )
    (net (code "102") (name "unconnected-(XB1-VREF-Pad14)") (class "Default")
      (node (ref "XB1") (pin "14") (pinfunction "VREF_14") (pintype "input"))
    )
    (net (code "103") (name "unconnected-(XB1-~{CTS}{slash}DIO7-Pad12)") (class "Default")
      (node (ref "XB1") (pin "12") (pinfunction "~{CTS}/DIO7_12") (pintype "bidirectional"))
    )
    (net (code "104") (name "unconnected-(XB1-~{DTR}{slash}SLEEP_RQ{slash}DI8-Pad9)") (class "Default")
      (node (ref "XB1") (pin "9") (pinfunction "~{DTR}/SLEEP_RQ/DI8_9") (pintype "bidirectional"))
    )
    (net (code "105") (name "unconnected-(XB1-~{RESET}-Pad5)") (class "Default")
      (node (ref "XB1") (pin "5") (pinfunction "~{RESET}_5") (pintype "input"))
    )
    (net (code "106") (name "unconnected-(XB1-~{RTS}{slash}AD6{slash}DIO6-Pad16)") (class "Default")
      (node (ref "XB1") (pin "16") (pinfunction "~{RTS}/AD6/DIO6_16") (pintype "bidirectional"))
    )
  )
)
